# connectors.net
KiCad netlist of a schematic drawn in Altium Designer
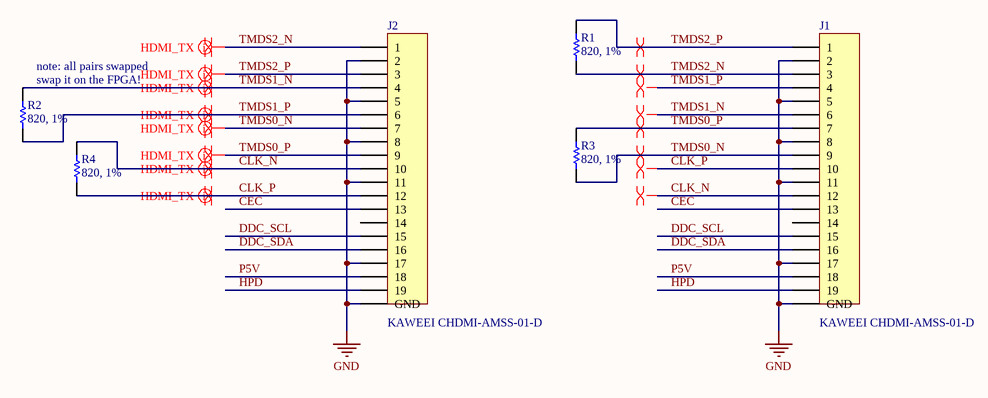
[diagram p0: connectors.SchDoc]

(export (version "E")
  (design (tool "Eeschema 10.0.6"))
  (components
    (comp (ref "J1")
      (value "KAWEEI CHDMI-AMSS-01-D")
      (footprint "KAWEEI_CHDMI_AMSS-01-D")
      (description "Molex HDMI connector, Type A")
      (fields (field (name "MPN") "CHDMI-AMSS-01-D") (field (name "PUBLISHER") "Altium Limited"))
      (libsource (lib "Miscellaneous Connectors") (part "Header 19"))
    )
    (comp (ref "J2")
      (value "KAWEEI CHDMI-AMSS-01-D")
      (footprint "KAWEEI_CHDMI_AMSS-01-D")
      (description "Molex HDMI connector, Type A")
      (fields (field (name "MPN") "CHDMI-AMSS-01-D") (field (name "PUBLISHER") "Altium Limited"))
      (libsource (lib "Miscellaneous Connectors") (part "Header 19"))
    )
    (comp (ref "R1")
      (value "820, 1%")
      (footprint "CAPC0603X03L")
      (description "Resistor")
      (fields (field (name "MPN") "ANY"))
      (libsource (lib "Miscellaneous Devices") (part "Res1"))
    )
    (comp (ref "R2")
      (value "820, 1%")
      (footprint "CAPC0603X03L")
      (description "Resistor")
      (fields (field (name "MPN") "ANY"))
      (libsource (lib "Miscellaneous Devices") (part "Res1"))
    )
    (comp (ref "R3")
      (value "820, 1%")
      (footprint "CAPC0603X03L")
      (description "Resistor")
      (fields (field (name "MPN") "ANY"))
      (libsource (lib "Miscellaneous Devices") (part "Res1"))
    )
    (comp (ref "R4")
      (value "820, 1%")
      (footprint "CAPC0603X03L")
      (description "Resistor")
      (fields (field (name "MPN") "ANY"))
      (libsource (lib "Miscellaneous Devices") (part "Res1"))
    )
  )
  (nets
    (net (code "1") (name "/CEC") (class "Default")
      (node (ref "J1") (pin "13") (pinfunction "13_13") (pintype "passive"))
      (node (ref "J2") (pin "13") (pinfunction "13_13") (pintype "passive"))
    )
    (net (code "2") (name "/CLK_N") (class "Default")
      (node (ref "J1") (pin "12") (pinfunction "12_12") (pintype "passive"))
      (node (ref "J2") (pin "10") (pinfunction "10_10") (pintype "passive"))
      (node (ref "R4") (pin "2") (pinfunction "2_2") (pintype "passive"))
    )
    (net (code "3") (name "/CLK_P") (class "Default")
      (node (ref "J1") (pin "10") (pinfunction "10_10") (pintype "passive"))
      (node (ref "J2") (pin "12") (pinfunction "12_12") (pintype "passive"))
      (node (ref "R4") (pin "1") (pinfunction "1_1") (pintype "passive"))
    )
    (net (code "4") (name "/DDC_SCL") (class "Default")
      (node (ref "J1") (pin "15") (pinfunction "15_15") (pintype "passive"))
      (node (ref "J2") (pin "15") (pinfunction "15_15") (pintype "passive"))
    )
    (net (code "5") (name "/DDC_SDA") (class "Default")
      (node (ref "J1") (pin "16") (pinfunction "16_16") (pintype "passive"))
      (node (ref "J2") (pin "16") (pinfunction "16_16") (pintype "passive"))
    )
    (net (code "6") (name "/HPD") (class "Default")
      (node (ref "J1") (pin "19") (pinfunction "19_19") (pintype "passive"))
      (node (ref "J2") (pin "19") (pinfunction "19_19") (pintype "passive"))
    )
    (net (code "7") (name "/P5V") (class "Default")
      (node (ref "J1") (pin "18") (pinfunction "18_18") (pintype "passive"))
      (node (ref "J2") (pin "18") (pinfunction "18_18") (pintype "passive"))
    )
    (net (code "8") (name "/TMDS0_N") (class "Default")
      (node (ref "J1") (pin "9") (pinfunction "9_9") (pintype "passive"))
      (node (ref "J2") (pin "7") (pinfunction "7_7") (pintype "passive"))
      (node (ref "R3") (pin "1") (pinfunction "1_1") (pintype "passive"))
    )
    (net (code "9") (name "/TMDS0_P") (class "Default")
      (node (ref "J1") (pin "7") (pinfunction "7_7") (pintype "passive"))
      (node (ref "J2") (pin "9") (pinfunction "9_9") (pintype "passive"))
      (node (ref "R3") (pin "2") (pinfunction "2_2") (pintype "passive"))
    )
    (net (code "10") (name "/TMDS1_N") (class "Default")
      (node (ref "J1") (pin "6") (pinfunction "6_6") (pintype "passive"))
      (node (ref "J2") (pin "4") (pinfunction "4_4") (pintype "passive"))
      (node (ref "R2") (pin "2") (pinfunction "2_2") (pintype "passive"))
    )
    (net (code "11") (name "/TMDS1_P") (class "Default")
      (node (ref "J1") (pin "4") (pinfunction "4_4") (pintype "passive"))
      (node (ref "J2") (pin "6") (pinfunction "6_6") (pintype "passive"))
      (node (ref "R2") (pin "1") (pinfunction "1_1") (pintype "passive"))
    )
    (net (code "12") (name "/TMDS2_N") (class "Default")
      (node (ref "J1") (pin "3") (pinfunction "3_3") (pintype "passive"))
      (node (ref "J2") (pin "1") (pinfunction "1_1") (pintype "passive"))
      (node (ref "R1") (pin "1") (pinfunction "1_1") (pintype "passive"))
    )
    (net (code "13") (name "/TMDS2_P") (class "Default")
      (node (ref "J1") (pin "1") (pinfunction "1_1") (pintype "passive"))
      (node (ref "J2") (pin "3") (pinfunction "3_3") (pintype "passive"))
      (node (ref "R1") (pin "2") (pinfunction "2_2") (pintype "passive"))
    )
    (net (code "14") (name "GND") (class "Default")
      (node (ref "J1") (pin "0") (pinfunction "GND_0") (pintype "passive"))
      (node (ref "J1") (pin "11") (pinfunction "11_11") (pintype "passive"))
      (node (ref "J1") (pin "17") (pinfunction "17_17") (pintype "passive"))
      (node (ref "J1") (pin "2") (pinfunction "2_2") (pintype "passive"))
      (node (ref "J1") (pin "5") (pinfunction "5_5") (pintype "passive"))
      (node (ref "J1") (pin "8") (pinfunction "8_8") (pintype "passive"))
      (node (ref "J2") (pin "0") (pinfunction "GND_0") (pintype "passive"))
      (node (ref "J2") (pin "11") (pinfunction "11_11") (pintype "passive"))
      (node (ref "J2") (pin "17") (pinfunction "17_17") (pintype "passive"))
      (node (ref "J2") (pin "2") (pinfunction "2_2") (pintype "passive"))
      (node (ref "J2") (pin "5") (pinfunction "5_5") (pintype "passive"))
      (node (ref "J2") (pin "8") (pinfunction "8_8") (pintype "passive"))
    )
    (net (code "15") (name "unconnected-(J1-Pad14)") (class "Default")
      (node (ref "J1") (pin "14") (pinfunction "14_14") (pintype "passive"))
    )
    (net (code "16") (name "unconnected-(J2-Pad14)") (class "Default")
      (node (ref "J2") (pin "14") (pinfunction "14_14") (pintype "passive"))
    )
  )
)
